# D1_Mini_Power_Shield_V1_0.net
KiCad netlist of a schematic drawn in EAGLE
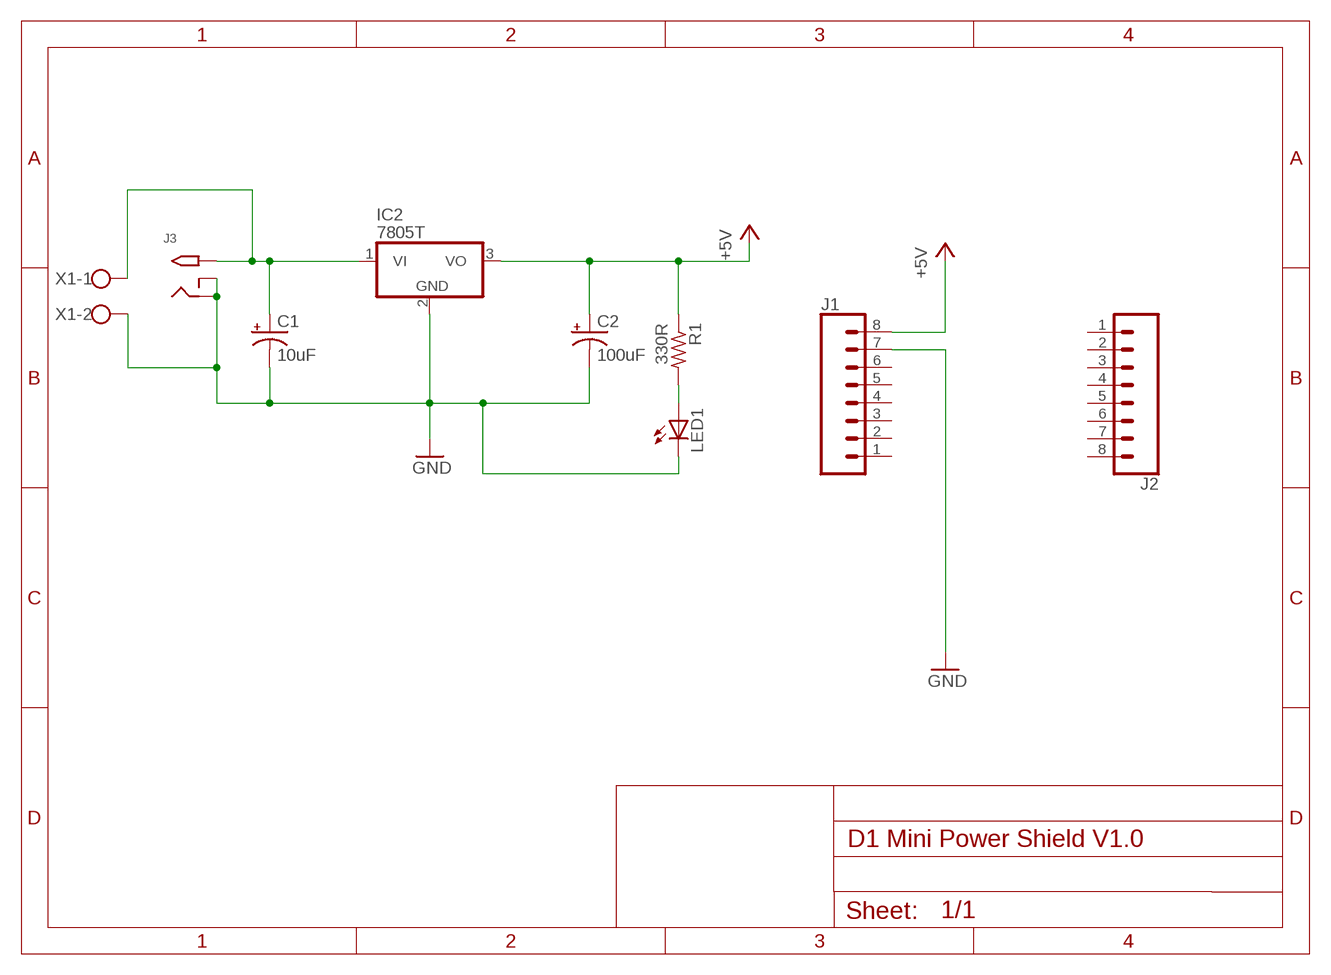
[diagram p0: schematic, sheet 1]

(export (version "E")
  (design (tool "Eeschema 10.0.6"))
  (components
    (comp (ref "C1")
      (value "10uF")
      (footprint "eagle-import:E2,5-7")
      (libsource (lib "eagle-import") (part "CPOL-USE2.5-7"))
    )
    (comp (ref "C2")
      (value "100uF")
      (footprint "eagle-import:E2,5-7")
      (libsource (lib "eagle-import") (part "CPOL-USE2.5-7"))
    )
    (comp (ref "IC2")
      (value "7805T")
      (footprint "eagle-import:TO220H")
      (libsource (lib "eagle-import") (part "78T05"))
    )
    (comp (ref "J1")
      (value "CONN_08\"")
      (footprint "eagle-import:1X08")
      (libsource (lib "eagle-import") (part "CONN_08{dblquote}"))
    )
    (comp (ref "J2")
      (value "CONN_08\"")
      (footprint "eagle-import:1X08")
      (libsource (lib "eagle-import") (part "CONN_08{dblquote}"))
    )
    (comp (ref "J3")
      (value "2.1MMJACKTHM")
      (footprint "eagle-import:PJ-102A")
      (libsource (lib "eagle-import") (part "2.1MMJACKTHM"))
    )
    (comp (ref "LED1")
      (value "LED3MM")
      (footprint "eagle-import:LED3MM")
      (libsource (lib "eagle-import") (part "LED3MM"))
    )
    (comp (ref "R1")
      (value "330R")
      (footprint "eagle-import:0207_2V")
      (libsource (lib "eagle-import") (part "R-US_0207/2V"))
    )
    (comp (ref "X1")
      (value "W237-102")
      (footprint "eagle-import:W237-102")
      (fields (field (name "MPN") "237-102"))
      (libsource (lib "eagle-import") (part "W237-102"))
    )
  )
  (nets
    (net (code "1") (name "+5V") (class "Default")
      (node (ref "C2") (pin "+") (pinfunction "+_+") (pintype "passive"))
      (node (ref "IC2") (pin "3") (pinfunction "VO_3") (pintype "passive"))
      (node (ref "J1") (pin "8") (pinfunction "8_8") (pintype "passive"))
      (node (ref "R1") (pin "1") (pinfunction "1_1") (pintype "passive"))
    )
    (net (code "2") (name "GND") (class "Default")
      (node (ref "C1") (pin "-") (pinfunction "-_-") (pintype "passive"))
      (node (ref "C2") (pin "-") (pinfunction "-_-") (pintype "passive"))
      (node (ref "IC2") (pin "2") (pinfunction "GND_2") (pintype "passive"))
      (node (ref "J1") (pin "7") (pinfunction "7_7") (pintype "passive"))
      (node (ref "J3") (pin "RING") (pinfunction "RING_RING") (pintype "bidirectional"))
      (node (ref "J3") (pin "RING_SW") (pinfunction "RING_SW_RING_SW") (pintype "bidirectional"))
      (node (ref "LED1") (pin "K") (pinfunction "C_K") (pintype "passive"))
      (node (ref "X1") (pin "2") (pinfunction "KL_2") (pintype "passive"))
    )
    (net (code "3") (name "Net-(IC2-VI)") (class "Default")
      (node (ref "C1") (pin "+") (pinfunction "+_+") (pintype "passive"))
      (node (ref "IC2") (pin "1") (pinfunction "VI_1") (pintype "input"))
      (node (ref "J3") (pin "TIP") (pinfunction "TIP_TIP") (pintype "bidirectional"))
      (node (ref "X1") (pin "1") (pinfunction "KL_1") (pintype "passive"))
    )
    (net (code "4") (name "Net-(LED1-PadA)") (class "Default")
      (node (ref "LED1") (pin "A") (pinfunction "A_A") (pintype "passive"))
      (node (ref "R1") (pin "2") (pinfunction "2_2") (pintype "passive"))
    )
    (net (code "5") (name "unconnected-(J1-Pad1)") (class "Default")
      (node (ref "J1") (pin "1") (pinfunction "1_1") (pintype "passive"))
    )
    (net (code "6") (name "unconnected-(J1-Pad2)") (class "Default")
      (node (ref "J1") (pin "2") (pinfunction "2_2") (pintype "passive"))
    )
    (net (code "7") (name "unconnected-(J1-Pad3)") (class "Default")
      (node (ref "J1") (pin "3") (pinfunction "3_3") (pintype "passive"))
    )
    (net (code "8") (name "unconnected-(J1-Pad4)") (class "Default")
      (node (ref "J1") (pin "4") (pinfunction "4_4") (pintype "passive"))
    )
    (net (code "9") (name "unconnected-(J1-Pad5)") (class "Default")
      (node (ref "J1") (pin "5") (pinfunction "5_5") (pintype "passive"))
    )
    (net (code "10") (name "unconnected-(J1-Pad6)") (class "Default")
      (node (ref "J1") (pin "6") (pinfunction "6_6") (pintype "passive"))
    )
    (net (code "11") (name "unconnected-(J2-Pad1)") (class "Default")
      (node (ref "J2") (pin "1") (pinfunction "1_1") (pintype "passive"))
    )
    (net (code "12") (name "unconnected-(J2-Pad2)") (class "Default")
      (node (ref "J2") (pin "2") (pinfunction "2_2") (pintype "passive"))
    )
    (net (code "13") (name "unconnected-(J2-Pad3)") (class "Default")
      (node (ref "J2") (pin "3") (pinfunction "3_3") (pintype "passive"))
    )
    (net (code "14") (name "unconnected-(J2-Pad4)") (class "Default")
      (node (ref "J2") (pin "4") (pinfunction "4_4") (pintype "passive"))
    )
    (net (code "15") (name "unconnected-(J2-Pad5)") (class "Default")
      (node (ref "J2") (pin "5") (pinfunction "5_5") (pintype "passive"))
    )
    (net (code "16") (name "unconnected-(J2-Pad6)") (class "Default")
      (node (ref "J2") (pin "6") (pinfunction "6_6") (pintype "passive"))
    )
    (net (code "17") (name "unconnected-(J2-Pad7)") (class "Default")
      (node (ref "J2") (pin "7") (pinfunction "7_7") (pintype "passive"))
    )
    (net (code "18") (name "unconnected-(J2-Pad8)") (class "Default")
      (node (ref "J2") (pin "8") (pinfunction "8_8") (pintype "passive"))
    )
  )
)
